# bluetooth.net
KiCad netlist of a schematic drawn in Altium Designer
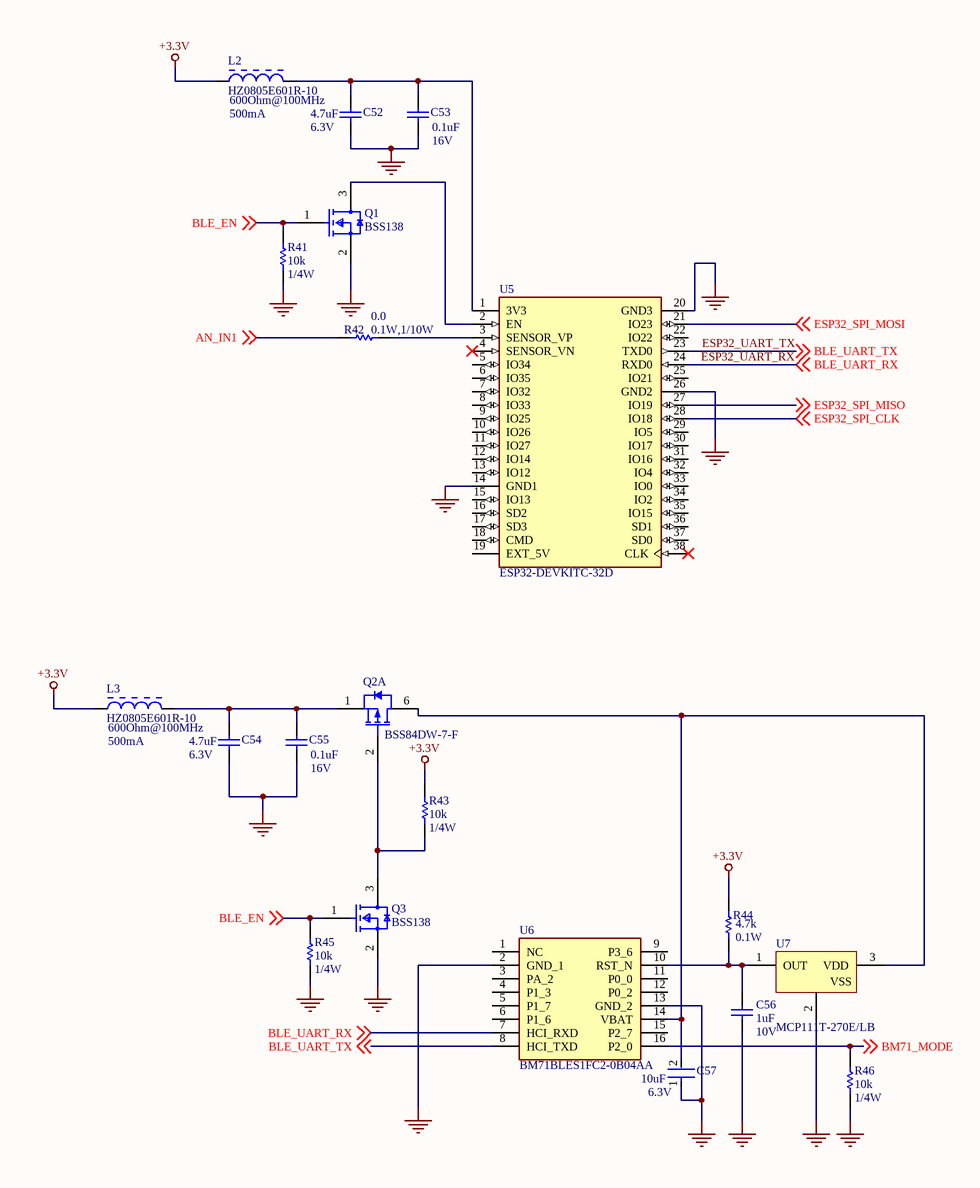
[diagram p0: bluetooth.SchDoc]

(export (version "E")
  (design (tool "Eeschema 10.0.6"))
  (components
    (comp (ref "C52")
      (value "4.7uF")
      (footprint "CAPC2013X145X50NL20T25")
      (fields
        (field (name "PART NUMBER") "C0805C475K9PACTU")
        (field (name "MANUFACTURER") "Kemet")
        (field (name "VOLTAGE") "6.3V")
      )
      (libsource (lib "Altium Content Vault") (part "CAP"))
    )
    (comp (ref "C53")
      (value "0.1uF")
      (footprint "CAPC1608X87X35ML15T15")
      (description "Ceramic Capacitor 0.1uF 16V +-10% X7R0603")
      (fields
        (field (name "PART NUMBER") "C0603C104M4RACTU")
        (field (name "MANUFACTURER") "Kemet")
        (field (name "VOLTAGE") "16V")
      )
      (libsource (lib "Altium Content Vault") (part "CAP"))
    )
    (comp (ref "C54")
      (value "4.7uF")
      (footprint "CAPC2013X145X50NL20T25")
      (fields
        (field (name "PART NUMBER") "C0805C475K9PACTU")
        (field (name "MANUFACTURER") "Kemet")
        (field (name "VOLTAGE") "6.3V")
      )
      (libsource (lib "Altium Content Vault") (part "CAP"))
    )
    (comp (ref "C55")
      (value "0.1uF")
      (footprint "CAPC1608X87X35ML15T15")
      (description "Ceramic Capacitor 0.1uF 16V +-10% X7R0603")
      (fields
        (field (name "PART NUMBER") "C0603C104M4RACTU")
        (field (name "MANUFACTURER") "Kemet")
        (field (name "VOLTAGE") "16V")
      )
      (libsource (lib "Altium Content Vault") (part "CAP"))
    )
    (comp (ref "C56")
      (value "1uF")
      (footprint "CAPC1608X90X35ML15T15")
      (fields
        (field (name "MANUFACTURER") "Kemet")
        (field (name "PART NUMBER") "C0603C105K8RACTU")
        (field (name "VOLTAGE") "10V")
      )
      (libsource (lib "Altium Content Vault") (part "CAP"))
    )
    (comp (ref "C57")
      (value "10uF")
      (footprint "FP-CL10-IPC_C")
      (description "Cap Ceramic 10uF 6.3V X5R ±20% Pad SMD 0603 +85°C T/R")
      (fields
        (field (name "VOLTAGE") "6.3V")
        (field (name "TOLERANCE") "20%")
        (field (name "MANUFACTURER") "Samsung")
      )
      (libsource (lib "Altium Content Vault") (part "b4654b650e69147ec39a6b967a45e02"))
    )
    (comp (ref "L2")
      (value "HZ0805E601R-10")
      (footprint "LIRD-LI0805H151R-10-2_V")
      (fields
        (field (name "IMPEDANCE @ FREQUENCY") "600Ohm@100MHz")
        (field (name "MANUFACTURER") "Laird")
        (field (name "CURRENT RATING (MAX)") "500mA")
      )
      (libsource (lib "Altium Content Vault") (part "IND-FB-2"))
    )
    (comp (ref "L3")
      (value "HZ0805E601R-10")
      (footprint "LIRD-LI0805H151R-10-2_V")
      (fields
        (field (name "IMPEDANCE @ FREQUENCY") "600Ohm@100MHz")
        (field (name "MANUFACTURER") "Laird")
        (field (name "CURRENT RATING (MAX)") "500mA")
      )
      (libsource (lib "Altium Content Vault") (part "IND-FB-2"))
    )
    (comp (ref "Q1")
      (value "BSS138")
      (footprint "FP-318-08-IPC_B")
      (description "MOSFET N-CH 50V 220MA SOT-23")
      (libsource (lib "Altium Content Vault") (part "3b9c635fedb024a5347a57b145af9cc"))
    )
    (comp (ref "Q2")
      (value "BSS84DW-7-F")
      (footprint "DIOD-SOT363-6_V")
      (description "Dual P-Channel Enhancement Mode MOSFET, 50 VDS, -55 to 150 degC, 6-Pin SOT363, RoHS, Tape and Reel")
      (fields (field (name "MANUFACTURER") "DiodesIncorporated"))
      (libsource (lib "Altium Content Vault") (part "PEMOS-SGD-SGD-6"))
    )
    (comp (ref "Q3")
      (value "BSS138")
      (footprint "FP-318-08-IPC_B")
      (description "MOSFET N-CH 50V 220MA SOT-23")
      (libsource (lib "Altium Content Vault") (part "3b9c635fedb024a5347a57b145af9cc"))
    )
    (comp (ref "R41")
      (value "10k")
      (footprint "RESC3216X70X50NL05T20")
      (description "Res Thick Film 1206 10k Ohms 5% 1/4W")
      (fields
        (field (name "PART NUMBER") "ERJ-8GEYJ103V")
        (field (name "MANUFACTURER") "Panasonic")
        (field (name "POWER") "1/4W")
      )
      (libsource (lib "Altium Content Vault") (part "RES"))
    )
    (comp (ref "R42")
      (value "0.0")
      (footprint "RESC1608X55X35LL10T10")
      (description "Chip Resistor, 0 Ohm, +/- 5%, 0.1 W, -55 to 155 degC, 0603 (1608 Metric), RoHS, Tape and Reel")
      (fields
        (field (name "POWER") "0.1W,1/10W")
        (field (name "MANUFACTURER") "Samsung-Electro-Mechanics-America,-Inc.")
        (field (name "TOLERANCE") "Jumper")
      )
      (libsource (lib "Altium Content Vault") (part "RES-2"))
    )
    (comp (ref "R43")
      (value "10k")
      (footprint "RESC3216X70X50NL05T20")
      (description "Res Thick Film 1206 10k Ohms 5% 1/4W")
      (fields
        (field (name "PART NUMBER") "ERJ-8GEYJ103V")
        (field (name "MANUFACTURER") "Panasonic")
        (field (name "POWER") "1/4W")
      )
      (libsource (lib "Altium Content Vault") (part "RES"))
    )
    (comp (ref "R44")
      (value "4.7k")
      (footprint "RESC1608X55X25LL10T15")
      (description "Chip Resistor, 4.7 KOhm, +/- 1%, 0.1 W, -55 to 155 degC, 0603 (1608 Metric), RoHS, Tape and Reel")
      (fields
        (field (name "POWER") "0.1W")
        (field (name "MANUFACTURER") "Yageo")
        (field (name "TOLERANCE") "1%")
      )
      (libsource (lib "Altium Content Vault") (part "RES-2"))
    )
    (comp (ref "R45")
      (value "10k")
      (footprint "RESC3216X70X50NL05T20")
      (description "Res Thick Film 1206 10k Ohms 5% 1/4W")
      (fields
        (field (name "PART NUMBER") "ERJ-8GEYJ103V")
        (field (name "MANUFACTURER") "Panasonic")
        (field (name "POWER") "1/4W")
      )
      (libsource (lib "Altium Content Vault") (part "RES"))
    )
    (comp (ref "R46")
      (value "10k")
      (footprint "RESC3216X70X50NL05T20")
      (description "Res Thick Film 1206 10k Ohms 5% 1/4W")
      (fields
        (field (name "PART NUMBER") "ERJ-8GEYJ103V")
        (field (name "MANUFACTURER") "Panasonic")
        (field (name "POWER") "1/4W")
      )
      (libsource (lib "Altium Content Vault") (part "RES"))
    )
    (comp (ref "U5")
      (value "ESP32-DEVKITC-32D")
      (footprint "MODULE_ESP32-DEVKITC-32D")
      (fields (field (name "MF") "Espressif Systems"))
      (libsource (lib "ESP32-DEVKITC-32D") (part "ESP32-DEVKITC-32D"))
    )
    (comp (ref "U6")
      (value "BM71BLES1FC2-0B04AA")
      (footprint "SamacSys:BM71BLES1FC2_1")
      (description "Integrated Circuit")
      (fields (field (name "MOUSER PART NUMBER") "579-BM71BS1FC2-BB04"))
      (libsource (lib "SamacSys") (part "BM71BLES1FC2-0B04AA"))
    )
    (comp (ref "U7")
      (value "MCP111T-270E/LB")
      (footprint "SC70-LB3_N")
      (libsource (lib "Altium Content Vault") (part "PM-VLTD-MCP11X-SOT3"))
    )
  )
  (nets
    (net (code "1") (name "+3.3V") (class "Default")
      (node (ref "L2") (pin "1") (pinfunction "1_1") (pintype "passive"))
      (node (ref "L3") (pin "1") (pinfunction "1_1") (pintype "passive"))
      (node (ref "R43") (pin "1") (pinfunction "1_1") (pintype "passive"))
      (node (ref "R44") (pin "2") (pinfunction "2_2") (pintype "passive"))
    )
    (net (code "2") (name "AN_IN1") (class "Default")
      (node (ref "R42") (pin "1") (pinfunction "1_1") (pintype "passive"))
    )
    (net (code "3") (name "BLE_EN") (class "Default")
      (node (ref "Q1") (pin "1") (pinfunction "G_1") (pintype "passive"))
      (node (ref "Q3") (pin "1") (pinfunction "G_1") (pintype "passive"))
      (node (ref "R41") (pin "1") (pinfunction "1_1") (pintype "passive"))
      (node (ref "R45") (pin "1") (pinfunction "1_1") (pintype "passive"))
    )
    (net (code "4") (name "BLE_UART_RX") (class "Default")
      (node (ref "U5") (pin "24") (pinfunction "RXD0_24") (pintype "input"))
      (node (ref "U6") (pin "7") (pinfunction "HCI_RXD_7") (pintype "passive"))
    )
    (net (code "5") (name "BLE_UART_TX") (class "Default")
      (node (ref "U5") (pin "23") (pinfunction "TXD0_23") (pintype "output"))
      (node (ref "U6") (pin "8") (pinfunction "HCI_TXD_8") (pintype "passive"))
    )
    (net (code "6") (name "BM71_MODE") (class "Default")
      (node (ref "R46") (pin "1") (pinfunction "1_1") (pintype "passive"))
      (node (ref "U6") (pin "16") (pinfunction "P2_0_16") (pintype "passive"))
    )
    (net (code "7") (name "ESP32_SPI_CLK") (class "Default")
      (node (ref "U5") (pin "28") (pinfunction "IO18_28") (pintype "bidirectional"))
    )
    (net (code "8") (name "ESP32_SPI_MISO") (class "Default")
      (node (ref "U5") (pin "27") (pinfunction "IO19_27") (pintype "bidirectional"))
    )
    (net (code "9") (name "ESP32_SPI_MOSI") (class "Default")
      (node (ref "U5") (pin "21") (pinfunction "IO23_21") (pintype "bidirectional"))
    )
    (net (code "10") (name "GND") (class "Default")
      (node (ref "C52") (pin "1") (pinfunction "1_1") (pintype "passive"))
      (node (ref "C53") (pin "1") (pinfunction "1_1") (pintype "passive"))
      (node (ref "C54") (pin "1") (pinfunction "1_1") (pintype "passive"))
      (node (ref "C55") (pin "1") (pinfunction "1_1") (pintype "passive"))
      (node (ref "C56") (pin "1") (pinfunction "1_1") (pintype "passive"))
      (node (ref "C57") (pin "1") (pinfunction "1_1") (pintype "passive"))
      (node (ref "Q1") (pin "2") (pinfunction "S_2") (pintype "passive"))
      (node (ref "Q3") (pin "2") (pinfunction "S_2") (pintype "passive"))
      (node (ref "R41") (pin "2") (pinfunction "2_2") (pintype "passive"))
      (node (ref "R45") (pin "2") (pinfunction "2_2") (pintype "passive"))
      (node (ref "R46") (pin "2") (pinfunction "2_2") (pintype "passive"))
      (node (ref "U5") (pin "14") (pinfunction "GND1_14") (pintype "power_in"))
      (node (ref "U5") (pin "20") (pinfunction "GND3_20") (pintype "power_in"))
      (node (ref "U5") (pin "26") (pinfunction "GND2_26") (pintype "power_in"))
      (node (ref "U6") (pin "13") (pinfunction "GND_2_13") (pintype "passive"))
      (node (ref "U6") (pin "2") (pinfunction "GND_1_2") (pintype "passive"))
      (node (ref "U7") (pin "2") (pinfunction "VSS_2") (pintype "power_in"))
    )
    (net (code "11") (name "Net-(Q1-D)") (class "Default")
      (node (ref "Q1") (pin "3") (pinfunction "D_3") (pintype "passive"))
      (node (ref "U5") (pin "2") (pinfunction "EN_2") (pintype "input"))
    )
    (net (code "12") (name "Net-(Q2A-D)") (class "Default")
      (node (ref "C57") (pin "2") (pinfunction "2_2") (pintype "passive"))
      (node (ref "Q2") (pin "6") (pinfunction "D_6") (pintype "passive"))
      (node (ref "U6") (pin "14") (pinfunction "VBAT_14") (pintype "passive"))
      (node (ref "U7") (pin "3") (pinfunction "VDD_3") (pintype "power_in"))
    )
    (net (code "13") (name "Net-(Q2A-G)") (class "Default")
      (node (ref "Q2") (pin "2") (pinfunction "G_2") (pintype "passive"))
      (node (ref "Q3") (pin "3") (pinfunction "D_3") (pintype "passive"))
      (node (ref "R43") (pin "2") (pinfunction "2_2") (pintype "passive"))
    )
    (net (code "14") (name "Net-(Q2A-S)") (class "Default")
      (node (ref "C54") (pin "2") (pinfunction "2_2") (pintype "passive"))
      (node (ref "C55") (pin "2") (pinfunction "2_2") (pintype "passive"))
      (node (ref "L3") (pin "2") (pinfunction "2_2") (pintype "passive"))
      (node (ref "Q2") (pin "1") (pinfunction "S_1") (pintype "passive"))
    )
    (net (code "15") (name "Net-(U5-3V3)") (class "Default")
      (node (ref "C52") (pin "2") (pinfunction "2_2") (pintype "passive"))
      (node (ref "C53") (pin "2") (pinfunction "2_2") (pintype "passive"))
      (node (ref "L2") (pin "2") (pinfunction "2_2") (pintype "passive"))
      (node (ref "U5") (pin "1") (pinfunction "3V3_1") (pintype "power_in"))
    )
    (net (code "16") (name "Net-(U5-SENSOR_VP)") (class "Default")
      (node (ref "R42") (pin "2") (pinfunction "2_2") (pintype "passive"))
      (node (ref "U5") (pin "3") (pinfunction "SENSOR_VP_3") (pintype "input"))
    )
    (net (code "17") (name "Net-(U6-RST_N)") (class "Default")
      (node (ref "C56") (pin "2") (pinfunction "2_2") (pintype "passive"))
      (node (ref "R44") (pin "1") (pinfunction "1_1") (pintype "passive"))
      (node (ref "U6") (pin "10") (pinfunction "RST_N_10") (pintype "passive"))
      (node (ref "U7") (pin "1") (pinfunction "OUT_1") (pintype "power_in"))
    )
    (net (code "18") (name "unconnected-(U5-CLK-Pad38)") (class "Default")
      (node (ref "U5") (pin "38") (pinfunction "CLK_38") (pintype "input+no_connect"))
    )
    (net (code "19") (name "unconnected-(U5-CMD-Pad18)") (class "Default")
      (node (ref "U5") (pin "18") (pinfunction "CMD_18") (pintype "bidirectional"))
    )
    (net (code "20") (name "unconnected-(U5-EXT_5V-Pad19)") (class "Default")
      (node (ref "U5") (pin "19") (pinfunction "EXT_5V_19") (pintype "power_in"))
    )
    (net (code "21") (name "unconnected-(U5-IO0-Pad33)") (class "Default")
      (node (ref "U5") (pin "33") (pinfunction "IO0_33") (pintype "bidirectional"))
    )
    (net (code "22") (name "unconnected-(U5-IO2-Pad34)") (class "Default")
      (node (ref "U5") (pin "34") (pinfunction "IO2_34") (pintype "bidirectional"))
    )
    (net (code "23") (name "unconnected-(U5-IO4-Pad32)") (class "Default")
      (node (ref "U5") (pin "32") (pinfunction "IO4_32") (pintype "bidirectional"))
    )
    (net (code "24") (name "unconnected-(U5-IO5-Pad29)") (class "Default")
      (node (ref "U5") (pin "29") (pinfunction "IO5_29") (pintype "bidirectional"))
    )
    (net (code "25") (name "unconnected-(U5-IO12-Pad13)") (class "Default")
      (node (ref "U5") (pin "13") (pinfunction "IO12_13") (pintype "bidirectional"))
    )
    (net (code "26") (name "unconnected-(U5-IO13-Pad15)") (class "Default")
      (node (ref "U5") (pin "15") (pinfunction "IO13_15") (pintype "bidirectional"))
    )
    (net (code "27") (name "unconnected-(U5-IO14-Pad12)") (class "Default")
      (node (ref "U5") (pin "12") (pinfunction "IO14_12") (pintype "bidirectional"))
    )
    (net (code "28") (name "unconnected-(U5-IO15-Pad35)") (class "Default")
      (node (ref "U5") (pin "35") (pinfunction "IO15_35") (pintype "bidirectional"))
    )
    (net (code "29") (name "unconnected-(U5-IO16-Pad31)") (class "Default")
      (node (ref "U5") (pin "31") (pinfunction "IO16_31") (pintype "bidirectional"))
    )
    (net (code "30") (name "unconnected-(U5-IO17-Pad30)") (class "Default")
      (node (ref "U5") (pin "30") (pinfunction "IO17_30") (pintype "bidirectional"))
    )
    (net (code "31") (name "unconnected-(U5-IO21-Pad25)") (class "Default")
      (node (ref "U5") (pin "25") (pinfunction "IO21_25") (pintype "bidirectional"))
    )
    (net (code "32") (name "unconnected-(U5-IO22-Pad22)") (class "Default")
      (node (ref "U5") (pin "22") (pinfunction "IO22_22") (pintype "bidirectional"))
    )
    (net (code "33") (name "unconnected-(U5-IO25-Pad9)") (class "Default")
      (node (ref "U5") (pin "9") (pinfunction "IO25_9") (pintype "bidirectional"))
    )
    (net (code "34") (name "unconnected-(U5-IO26-Pad10)") (class "Default")
      (node (ref "U5") (pin "10") (pinfunction "IO26_10") (pintype "bidirectional"))
    )
    (net (code "35") (name "unconnected-(U5-IO27-Pad11)") (class "Default")
      (node (ref "U5") (pin "11") (pinfunction "IO27_11") (pintype "bidirectional"))
    )
    (net (code "36") (name "unconnected-(U5-IO32-Pad7)") (class "Default")
      (node (ref "U5") (pin "7") (pinfunction "IO32_7") (pintype "bidirectional"))
    )
    (net (code "37") (name "unconnected-(U5-IO33-Pad8)") (class "Default")
      (node (ref "U5") (pin "8") (pinfunction "IO33_8") (pintype "bidirectional"))
    )
    (net (code "38") (name "unconnected-(U5-IO34-Pad5)") (class "Default")
      (node (ref "U5") (pin "5") (pinfunction "IO34_5") (pintype "bidirectional"))
    )
    (net (code "39") (name "unconnected-(U5-IO35-Pad6)") (class "Default")
      (node (ref "U5") (pin "6") (pinfunction "IO35_6") (pintype "bidirectional"))
    )
    (net (code "40") (name "unconnected-(U5-SD0-Pad37)") (class "Default")
      (node (ref "U5") (pin "37") (pinfunction "SD0_37") (pintype "bidirectional"))
    )
    (net (code "41") (name "unconnected-(U5-SD1-Pad36)") (class "Default")
      (node (ref "U5") (pin "36") (pinfunction "SD1_36") (pintype "bidirectional"))
    )
    (net (code "42") (name "unconnected-(U5-SD2-Pad16)") (class "Default")
      (node (ref "U5") (pin "16") (pinfunction "SD2_16") (pintype "bidirectional"))
    )
    (net (code "43") (name "unconnected-(U5-SD3-Pad17)") (class "Default")
      (node (ref "U5") (pin "17") (pinfunction "SD3_17") (pintype "bidirectional"))
    )
    (net (code "44") (name "unconnected-(U5-SENSOR_VN-Pad4)") (class "Default")
      (node (ref "U5") (pin "4") (pinfunction "SENSOR_VN_4") (pintype "input+no_connect"))
    )
    (net (code "45") (name "unconnected-(U6-NC-Pad1)") (class "Default")
      (node (ref "U6") (pin "1") (pinfunction "NC_1") (pintype "passive"))
    )
    (net (code "46") (name "unconnected-(U6-P0_0-Pad11)") (class "Default")
      (node (ref "U6") (pin "11") (pinfunction "P0_0_11") (pintype "passive"))
    )
    (net (code "47") (name "unconnected-(U6-P0_2-Pad12)") (class "Default")
      (node (ref "U6") (pin "12") (pinfunction "P0_2_12") (pintype "passive"))
    )
    (net (code "48") (name "unconnected-(U6-P1_3-Pad4)") (class "Default")
      (node (ref "U6") (pin "4") (pinfunction "P1_3_4") (pintype "passive"))
    )
    (net (code "49") (name "unconnected-(U6-P1_6-Pad6)") (class "Default")
      (node (ref "U6") (pin "6") (pinfunction "P1_6_6") (pintype "passive"))
    )
    (net (code "50") (name "unconnected-(U6-P1_7-Pad5)") (class "Default")
      (node (ref "U6") (pin "5") (pinfunction "P1_7_5") (pintype "passive"))
    )
    (net (code "51") (name "unconnected-(U6-P2_7-Pad15)") (class "Default")
      (node (ref "U6") (pin "15") (pinfunction "P2_7_15") (pintype "passive"))
    )
    (net (code "52") (name "unconnected-(U6-P3_6-Pad9)") (class "Default")
      (node (ref "U6") (pin "9") (pinfunction "P3_6_9") (pintype "passive"))
    )
    (net (code "53") (name "unconnected-(U6-PA_2-Pad3)") (class "Default")
      (node (ref "U6") (pin "3") (pinfunction "PA_2_3") (pintype "passive"))
    )
  )
)
